# ti-tps61288-junctions-cleaned.net
KiCad netlist of a schematic drawn in Altium Designer
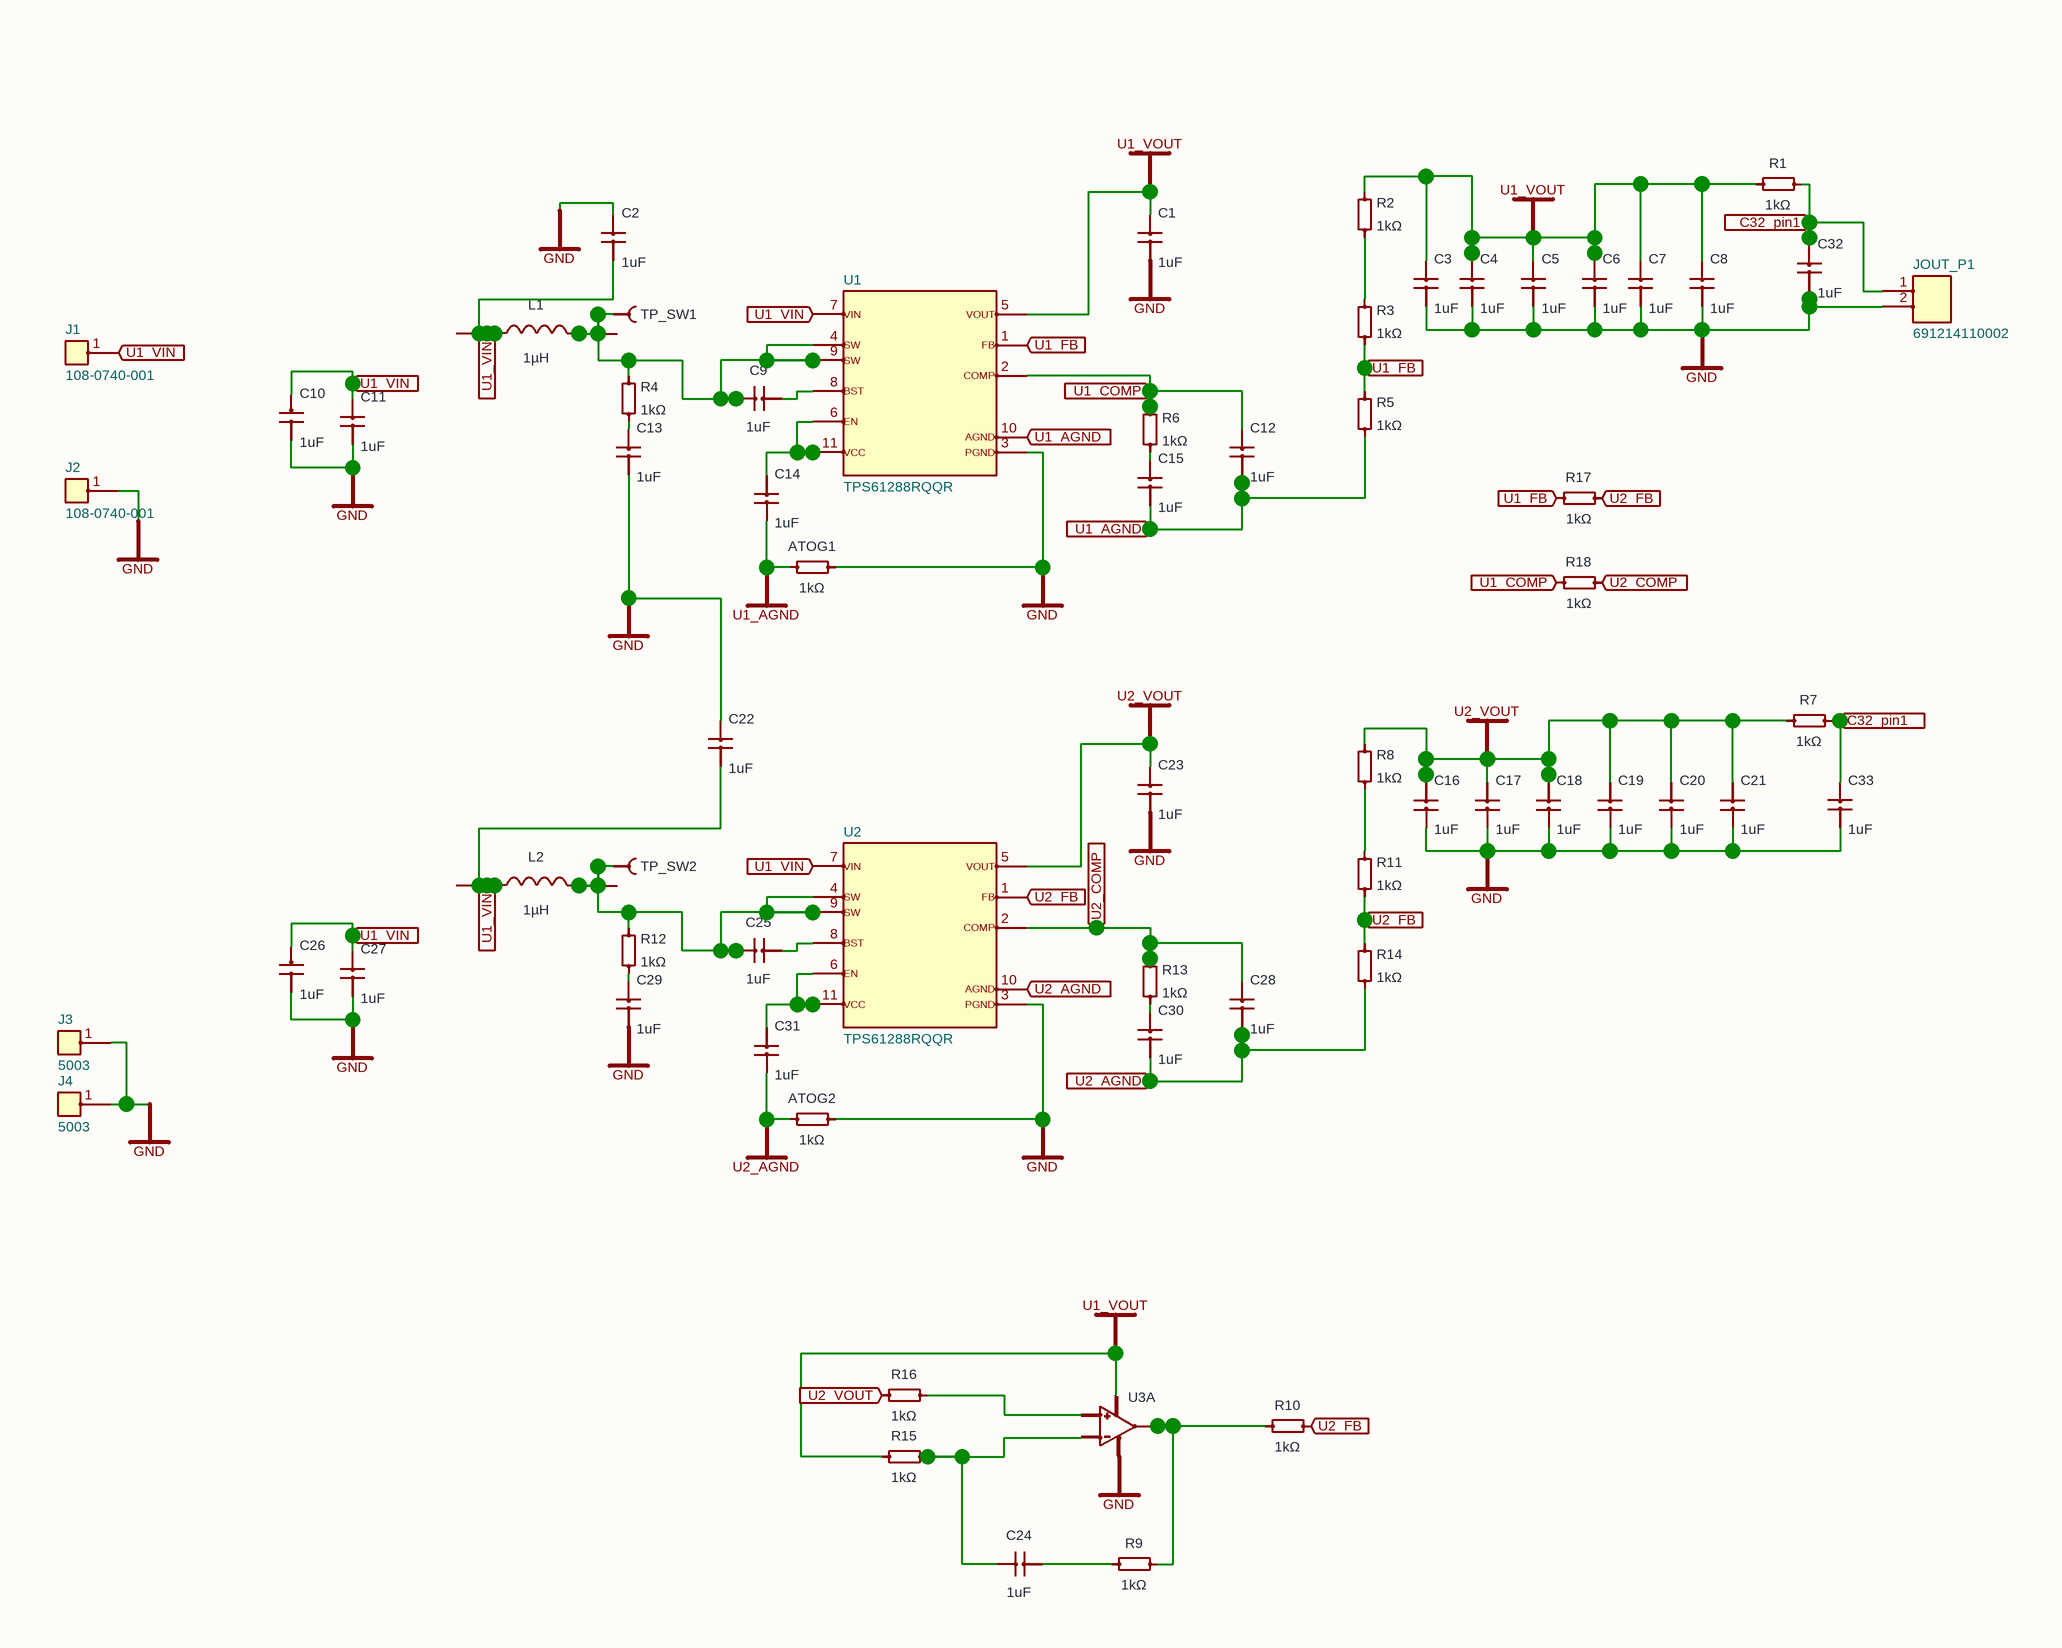
[diagram p0: ti-tps61288-junctions-cleaned.SchDoc]

(export (version "E")
  (design (tool "Eeschema 10.0.6"))
  (components
    (comp (ref "ATOG1") (value "1kΩ") (libsource (lib "altium-import") (part "root_0_boxresistor_left_")))
    (comp (ref "ATOG2") (value "1kΩ") (libsource (lib "altium-import") (part "root_0_boxresistor_left_")))
    (comp (ref "C1") (value "1uF") (libsource (lib "altium-import") (part "root_0_capacitor_down_")))
    (comp (ref "C2") (value "1uF") (libsource (lib "altium-import") (part "root_0_capacitor_down_")))
    (comp (ref "C3") (value "1uF") (libsource (lib "altium-import") (part "root_0_capacitor_down_")))
    (comp (ref "C4") (value "1uF") (libsource (lib "altium-import") (part "root_0_capacitor_down_")))
    (comp (ref "C5") (value "1uF") (libsource (lib "altium-import") (part "root_0_capacitor_down_")))
    (comp (ref "C6") (value "1uF") (libsource (lib "altium-import") (part "root_0_capacitor_down_")))
    (comp (ref "C7") (value "1uF") (libsource (lib "altium-import") (part "root_0_capacitor_down_")))
    (comp (ref "C8") (value "1uF") (libsource (lib "altium-import") (part "root_0_capacitor_down_")))
    (comp (ref "C9") (value "1uF") (libsource (lib "altium-import") (part "root_0_capacitor_right_")))
    (comp (ref "C10") (value "1uF") (libsource (lib "") (part "root_0_capacitor_down__1")))
    (comp (ref "C11") (value "1uF") (libsource (lib "altium-import") (part "root_0_capacitor_down_")))
    (comp (ref "C12") (value "1uF") (libsource (lib "altium-import") (part "root_0_capacitor_down_")))
    (comp (ref "C13") (value "1uF") (libsource (lib "altium-import") (part "root_0_capacitor_down_")))
    (comp (ref "C14") (value "1uF") (libsource (lib "altium-import") (part "root_0_capacitor_up_")))
    (comp (ref "C15") (value "1uF") (libsource (lib "altium-import") (part "root_0_capacitor_down_")))
    (comp (ref "C16") (value "1uF") (libsource (lib "altium-import") (part "root_0_capacitor_up_")))
    (comp (ref "C17") (value "1uF") (libsource (lib "altium-import") (part "root_0_capacitor_up_")))
    (comp (ref "C18") (value "1uF") (libsource (lib "altium-import") (part "root_0_capacitor_up_")))
    (comp (ref "C19") (value "1uF") (libsource (lib "altium-import") (part "root_0_capacitor_up_")))
    (comp (ref "C20") (value "1uF") (libsource (lib "altium-import") (part "root_0_capacitor_up_")))
    (comp (ref "C21") (value "1uF") (libsource (lib "altium-import") (part "root_0_capacitor_up_")))
    (comp (ref "C22") (value "1uF") (libsource (lib "altium-import") (part "root_0_capacitor_down_")))
    (comp (ref "C23") (value "1uF") (libsource (lib "altium-import") (part "root_0_capacitor_down_")))
    (comp (ref "C24") (value "1uF") (libsource (lib "altium-import") (part "root_0_capacitor_left_")))
    (comp (ref "C25") (value "1uF") (libsource (lib "altium-import") (part "root_0_capacitor_right_")))
    (comp (ref "C26") (value "1uF") (libsource (lib "") (part "root_0_capacitor_down__1")))
    (comp (ref "C27") (value "1uF") (libsource (lib "altium-import") (part "root_0_capacitor_down_")))
    (comp (ref "C28") (value "1uF") (libsource (lib "altium-import") (part "root_0_capacitor_down_")))
    (comp (ref "C29") (value "1uF") (libsource (lib "altium-import") (part "root_0_capacitor_down_")))
    (comp (ref "C30") (value "1uF") (libsource (lib "altium-import") (part "root_0_capacitor_down_")))
    (comp (ref "C31") (value "1uF") (libsource (lib "altium-import") (part "root_0_capacitor_up_")))
    (comp (ref "C32") (value "1uF") (libsource (lib "altium-import") (part "root_0_capacitor_down_")))
    (comp (ref "C33") (value "1uF") (libsource (lib "altium-import") (part "root_0_capacitor_down_")))
    (comp (ref "J1") (value "~") (libsource (lib "altium-import") (part "root_0_J1_")))
    (comp (ref "J2") (value "~") (libsource (lib "altium-import") (part "root_0_J2_")))
    (comp (ref "J3") (value "~") (libsource (lib "altium-import") (part "root_0_J3_")))
    (comp (ref "J4") (value "~") (libsource (lib "altium-import") (part "root_0_J4_")))
    (comp (ref "JOUT_P1") (value "~") (libsource (lib "altium-import") (part "root_0_JOUT_P1_")))
    (comp (ref "L1") (value "1µH") (libsource (lib "altium-import") (part "root_0_inductor_right_")))
    (comp (ref "L2") (value "1µH") (libsource (lib "altium-import") (part "root_0_inductor_right_")))
    (comp (ref "R1") (value "1kΩ") (libsource (lib "altium-import") (part "root_0_boxresistor_right_")))
    (comp (ref "R2") (value "1kΩ") (libsource (lib "altium-import") (part "root_0_boxresistor_up_")))
    (comp (ref "R3") (value "1kΩ") (libsource (lib "altium-import") (part "root_0_boxresistor_up_")))
    (comp (ref "R4") (value "1kΩ") (libsource (lib "altium-import") (part "root_0_boxresistor_down_")))
    (comp (ref "R5") (value "1kΩ") (libsource (lib "altium-import") (part "root_0_boxresistor_down_")))
    (comp (ref "R6") (value "1kΩ") (libsource (lib "altium-import") (part "root_0_boxresistor_up_")))
    (comp (ref "R7") (value "1kΩ") (libsource (lib "altium-import") (part "root_0_boxresistor_right_")))
    (comp (ref "R8") (value "1kΩ") (libsource (lib "altium-import") (part "root_0_boxresistor_down_")))
    (comp (ref "R9") (value "1kΩ") (libsource (lib "altium-import") (part "root_0_boxresistor_right_")))
    (comp (ref "R10") (value "1kΩ") (libsource (lib "altium-import") (part "root_0_boxresistor_right_")))
    (comp (ref "R11") (value "1kΩ") (libsource (lib "altium-import") (part "root_0_boxresistor_up_")))
    (comp (ref "R12") (value "1kΩ") (libsource (lib "altium-import") (part "root_0_boxresistor_down_")))
    (comp (ref "R13") (value "1kΩ") (libsource (lib "altium-import") (part "root_0_boxresistor_up_")))
    (comp (ref "R14") (value "1kΩ") (libsource (lib "altium-import") (part "root_0_boxresistor_down_")))
    (comp (ref "R15") (value "1kΩ") (libsource (lib "altium-import") (part "root_0_boxresistor_right_")))
    (comp (ref "R16") (value "1kΩ") (libsource (lib "altium-import") (part "root_0_boxresistor_right_")))
    (comp (ref "R17") (value "1kΩ") (libsource (lib "altium-import") (part "root_0_boxresistor_left_")))
    (comp (ref "R18") (value "1kΩ") (libsource (lib "altium-import") (part "root_0_boxresistor_left_")))
    (comp (ref "TP_SW1") (value "~") (libsource (lib "altium-import") (part "root_0_testpoint_right_")))
    (comp (ref "TP_SW2") (value "~") (libsource (lib "altium-import") (part "root_0_testpoint_right_")))
    (comp (ref "U1") (value "~") (libsource (lib "altium-import") (part "root_0_U1_")))
    (comp (ref "U2") (value "~") (libsource (lib "altium-import") (part "root_0_U2_")))
    (comp (ref "U3A") (value "~") (libsource (lib "altium-import") (part "root_0_opamp_with_power_right_")))
  )
  (nets
    (net (code "1") (name "/C32_pin1") (class "Default")
      (node (ref "C32") (pin "1") (pinfunction "anode_1") (pintype "passive"))
      (node (ref "C33") (pin "1") (pinfunction "anode_1") (pintype "passive"))
      (node (ref "JOUT_P1") (pin "1") (pinfunction "1_1") (pintype "passive"))
      (node (ref "R1") (pin "2") (pinfunction "cathode_2") (pintype "passive"))
      (node (ref "R7") (pin "2") (pinfunction "cathode_2") (pintype "passive"))
    )
    (net (code "2") (name "/U1_COMP") (class "Default")
      (node (ref "C12") (pin "1") (pinfunction "anode_1") (pintype "passive"))
      (node (ref "R18") (pin "2") (pinfunction "cathode_2") (pintype "passive"))
      (node (ref "R6") (pin "2") (pinfunction "cathode_2") (pintype "passive"))
      (node (ref "U1") (pin "2") (pinfunction "COMP_2") (pintype "passive"))
    )
    (net (code "3") (name "/U1_FB") (class "Default")
      (node (ref "R17") (pin "2") (pinfunction "cathode_2") (pintype "passive"))
      (node (ref "R3") (pin "1") (pinfunction "anode_1") (pintype "passive"))
      (node (ref "R5") (pin "1") (pinfunction "anode_1") (pintype "passive"))
      (node (ref "U1") (pin "1") (pinfunction "FB_1") (pintype "passive"))
    )
    (net (code "4") (name "/U1_VIN") (class "Default")
      (node (ref "C10") (pin "1") (pinfunction "anode_1") (pintype "passive"))
      (node (ref "C11") (pin "1") (pinfunction "anode_1") (pintype "passive"))
      (node (ref "C2") (pin "2") (pinfunction "cathode_2") (pintype "passive"))
      (node (ref "C22") (pin "2") (pinfunction "cathode_2") (pintype "passive"))
      (node (ref "C26") (pin "1") (pinfunction "anode_1") (pintype "passive"))
      (node (ref "C27") (pin "1") (pinfunction "anode_1") (pintype "passive"))
      (node (ref "J1") (pin "1") (pinfunction "1_1") (pintype "passive"))
      (node (ref "L1") (pin "1") (pinfunction "anode_1") (pintype "passive"))
      (node (ref "L2") (pin "1") (pinfunction "anode_1") (pintype "passive"))
      (node (ref "U1") (pin "7") (pinfunction "VIN_7") (pintype "passive"))
      (node (ref "U2") (pin "7") (pinfunction "VIN_7") (pintype "passive"))
    )
    (net (code "5") (name "/U2_COMP") (class "Default")
      (node (ref "C28") (pin "1") (pinfunction "anode_1") (pintype "passive"))
      (node (ref "R13") (pin "2") (pinfunction "cathode_2") (pintype "passive"))
      (node (ref "R18") (pin "1") (pinfunction "anode_1") (pintype "passive"))
      (node (ref "U2") (pin "2") (pinfunction "COMP_2") (pintype "passive"))
    )
    (net (code "6") (name "/U2_FB") (class "Default")
      (node (ref "R10") (pin "2") (pinfunction "cathode_2") (pintype "passive"))
      (node (ref "R11") (pin "1") (pinfunction "anode_1") (pintype "passive"))
      (node (ref "R14") (pin "1") (pinfunction "anode_1") (pintype "passive"))
      (node (ref "R17") (pin "1") (pinfunction "anode_1") (pintype "passive"))
      (node (ref "U2") (pin "1") (pinfunction "FB_1") (pintype "passive"))
    )
    (net (code "7") (name "GND") (class "Default")
      (node (ref "ATOG1") (pin "1") (pinfunction "anode_1") (pintype "passive"))
      (node (ref "ATOG2") (pin "1") (pinfunction "anode_1") (pintype "passive"))
      (node (ref "C1") (pin "2") (pinfunction "cathode_2") (pintype "passive"))
      (node (ref "C10") (pin "2") (pinfunction "cathode_2") (pintype "passive"))
      (node (ref "C11") (pin "2") (pinfunction "cathode_2") (pintype "passive"))
      (node (ref "C13") (pin "2") (pinfunction "cathode_2") (pintype "passive"))
      (node (ref "C16") (pin "1") (pinfunction "anode_1") (pintype "passive"))
      (node (ref "C17") (pin "1") (pinfunction "anode_1") (pintype "passive"))
      (node (ref "C18") (pin "1") (pinfunction "anode_1") (pintype "passive"))
      (node (ref "C19") (pin "1") (pinfunction "anode_1") (pintype "passive"))
      (node (ref "C2") (pin "1") (pinfunction "anode_1") (pintype "passive"))
      (node (ref "C20") (pin "1") (pinfunction "anode_1") (pintype "passive"))
      (node (ref "C21") (pin "1") (pinfunction "anode_1") (pintype "passive"))
      (node (ref "C22") (pin "1") (pinfunction "anode_1") (pintype "passive"))
      (node (ref "C23") (pin "2") (pinfunction "cathode_2") (pintype "passive"))
      (node (ref "C26") (pin "2") (pinfunction "cathode_2") (pintype "passive"))
      (node (ref "C27") (pin "2") (pinfunction "cathode_2") (pintype "passive"))
      (node (ref "C29") (pin "2") (pinfunction "cathode_2") (pintype "passive"))
      (node (ref "C3") (pin "2") (pinfunction "cathode_2") (pintype "passive"))
      (node (ref "C32") (pin "2") (pinfunction "cathode_2") (pintype "passive"))
      (node (ref "C33") (pin "2") (pinfunction "cathode_2") (pintype "passive"))
      (node (ref "C4") (pin "2") (pinfunction "cathode_2") (pintype "passive"))
      (node (ref "C5") (pin "2") (pinfunction "cathode_2") (pintype "passive"))
      (node (ref "C6") (pin "2") (pinfunction "cathode_2") (pintype "passive"))
      (node (ref "C7") (pin "2") (pinfunction "cathode_2") (pintype "passive"))
      (node (ref "C8") (pin "2") (pinfunction "cathode_2") (pintype "passive"))
      (node (ref "J2") (pin "1") (pinfunction "1_1") (pintype "passive"))
      (node (ref "J3") (pin "1") (pinfunction "1_1") (pintype "passive"))
      (node (ref "J4") (pin "1") (pinfunction "1_1") (pintype "passive"))
      (node (ref "JOUT_P1") (pin "2") (pinfunction "2_2") (pintype "passive"))
      (node (ref "U1") (pin "3") (pinfunction "PGND_3") (pintype "passive"))
      (node (ref "U2") (pin "3") (pinfunction "PGND_3") (pintype "passive"))
      (node (ref "U3A") (pin "3") (pinfunction "V-_3") (pintype "passive"))
    )
    (net (code "8") (name "Net-(C9-neg)") (class "Default")
      (node (ref "C9") (pin "2") (pinfunction "neg_2") (pintype "passive"))
      (node (ref "U1") (pin "8") (pinfunction "BST_8") (pintype "passive"))
    )
    (net (code "9") (name "Net-(C9-pos)") (class "Default")
      (node (ref "C9") (pin "1") (pinfunction "pos_1") (pintype "passive"))
      (node (ref "L1") (pin "2") (pinfunction "cathode_2") (pintype "passive"))
      (node (ref "R4") (pin "1") (pinfunction "anode_1") (pintype "passive"))
      (node (ref "TP_SW1") (pin "1") (pinfunction "pin1_1") (pintype "passive"))
      (node (ref "U1") (pin "4") (pinfunction "SW_4") (pintype "passive"))
      (node (ref "U1") (pin "9") (pinfunction "SW_9") (pintype "passive"))
    )
    (net (code "10") (name "Net-(C13-anode)") (class "Default")
      (node (ref "C13") (pin "1") (pinfunction "anode_1") (pintype "passive"))
      (node (ref "R4") (pin "2") (pinfunction "cathode_2") (pintype "passive"))
    )
    (net (code "11") (name "Net-(C14-cathode)") (class "Default")
      (node (ref "C14") (pin "2") (pinfunction "cathode_2") (pintype "passive"))
      (node (ref "U1") (pin "11") (pinfunction "VCC_11") (pintype "passive"))
      (node (ref "U1") (pin "6") (pinfunction "EN_6") (pintype "passive"))
    )
    (net (code "12") (name "Net-(C15-anode)") (class "Default")
      (node (ref "C15") (pin "1") (pinfunction "anode_1") (pintype "passive"))
      (node (ref "R6") (pin "1") (pinfunction "anode_1") (pintype "passive"))
    )
    (net (code "13") (name "Net-(C24-neg)") (class "Default")
      (node (ref "C24") (pin "2") (pinfunction "neg_2") (pintype "passive"))
      (node (ref "R15") (pin "2") (pinfunction "cathode_2") (pintype "passive"))
      (node (ref "U3A") (pin "2") (pinfunction "inp2_2") (pintype "passive"))
    )
    (net (code "14") (name "Net-(C24-pos)") (class "Default")
      (node (ref "C24") (pin "1") (pinfunction "pos_1") (pintype "passive"))
      (node (ref "R9") (pin "1") (pinfunction "anode_1") (pintype "passive"))
    )
    (net (code "15") (name "Net-(C25-neg)") (class "Default")
      (node (ref "C25") (pin "2") (pinfunction "neg_2") (pintype "passive"))
      (node (ref "U2") (pin "8") (pinfunction "BST_8") (pintype "passive"))
    )
    (net (code "16") (name "Net-(C25-pos)") (class "Default")
      (node (ref "C25") (pin "1") (pinfunction "pos_1") (pintype "passive"))
      (node (ref "L2") (pin "2") (pinfunction "cathode_2") (pintype "passive"))
      (node (ref "R12") (pin "1") (pinfunction "anode_1") (pintype "passive"))
      (node (ref "TP_SW2") (pin "1") (pinfunction "pin1_1") (pintype "passive"))
      (node (ref "U2") (pin "4") (pinfunction "SW_4") (pintype "passive"))
      (node (ref "U2") (pin "9") (pinfunction "SW_9") (pintype "passive"))
    )
    (net (code "17") (name "Net-(C29-anode)") (class "Default")
      (node (ref "C29") (pin "1") (pinfunction "anode_1") (pintype "passive"))
      (node (ref "R12") (pin "2") (pinfunction "cathode_2") (pintype "passive"))
    )
    (net (code "18") (name "Net-(C30-anode)") (class "Default")
      (node (ref "C30") (pin "1") (pinfunction "anode_1") (pintype "passive"))
      (node (ref "R13") (pin "1") (pinfunction "anode_1") (pintype "passive"))
    )
    (net (code "19") (name "Net-(C31-cathode)") (class "Default")
      (node (ref "C31") (pin "2") (pinfunction "cathode_2") (pintype "passive"))
      (node (ref "U2") (pin "11") (pinfunction "VCC_11") (pintype "passive"))
      (node (ref "U2") (pin "6") (pinfunction "EN_6") (pintype "passive"))
    )
    (net (code "20") (name "Net-(R2-anode)") (class "Default")
      (node (ref "R2") (pin "1") (pinfunction "anode_1") (pintype "passive"))
      (node (ref "R3") (pin "2") (pinfunction "cathode_2") (pintype "passive"))
    )
    (net (code "21") (name "Net-(R10-anode)") (class "Default")
      (node (ref "R10") (pin "1") (pinfunction "anode_1") (pintype "passive"))
      (node (ref "R9") (pin "2") (pinfunction "cathode_2") (pintype "passive"))
      (node (ref "U3A") (pin "4") (pinfunction "out_4") (pintype "passive"))
    )
    (net (code "22") (name "Net-(R11-cathode)") (class "Default")
      (node (ref "R11") (pin "2") (pinfunction "cathode_2") (pintype "passive"))
      (node (ref "R8") (pin "2") (pinfunction "cathode_2") (pintype "passive"))
    )
    (net (code "23") (name "Net-(R16-cathode)") (class "Default")
      (node (ref "R16") (pin "2") (pinfunction "cathode_2") (pintype "passive"))
      (node (ref "U3A") (pin "1") (pinfunction "inp1_1") (pintype "passive"))
    )
    (net (code "24") (name "U1_AGND") (class "Default")
      (node (ref "ATOG1") (pin "2") (pinfunction "cathode_2") (pintype "passive"))
      (node (ref "C12") (pin "2") (pinfunction "cathode_2") (pintype "passive"))
      (node (ref "C14") (pin "1") (pinfunction "anode_1") (pintype "passive"))
      (node (ref "C15") (pin "2") (pinfunction "cathode_2") (pintype "passive"))
      (node (ref "R5") (pin "2") (pinfunction "cathode_2") (pintype "passive"))
      (node (ref "U1") (pin "10") (pinfunction "AGND_10") (pintype "passive"))
    )
    (net (code "25") (name "U1_VOUT") (class "Default")
      (node (ref "C1") (pin "1") (pinfunction "anode_1") (pintype "passive"))
      (node (ref "C3") (pin "1") (pinfunction "anode_1") (pintype "passive"))
      (node (ref "C4") (pin "1") (pinfunction "anode_1") (pintype "passive"))
      (node (ref "C5") (pin "1") (pinfunction "anode_1") (pintype "passive"))
      (node (ref "C6") (pin "1") (pinfunction "anode_1") (pintype "passive"))
      (node (ref "C7") (pin "1") (pinfunction "anode_1") (pintype "passive"))
      (node (ref "C8") (pin "1") (pinfunction "anode_1") (pintype "passive"))
      (node (ref "R1") (pin "1") (pinfunction "anode_1") (pintype "passive"))
      (node (ref "R15") (pin "1") (pinfunction "anode_1") (pintype "passive"))
      (node (ref "R2") (pin "2") (pinfunction "cathode_2") (pintype "passive"))
      (node (ref "U1") (pin "5") (pinfunction "VOUT_5") (pintype "passive"))
      (node (ref "U3A") (pin "5") (pinfunction "V+_5") (pintype "passive"))
    )
    (net (code "26") (name "U2_AGND") (class "Default")
      (node (ref "ATOG2") (pin "2") (pinfunction "cathode_2") (pintype "passive"))
      (node (ref "C28") (pin "2") (pinfunction "cathode_2") (pintype "passive"))
      (node (ref "C30") (pin "2") (pinfunction "cathode_2") (pintype "passive"))
      (node (ref "C31") (pin "1") (pinfunction "anode_1") (pintype "passive"))
      (node (ref "R14") (pin "2") (pinfunction "cathode_2") (pintype "passive"))
      (node (ref "U2") (pin "10") (pinfunction "AGND_10") (pintype "passive"))
    )
    (net (code "27") (name "U2_VOUT") (class "Default")
      (node (ref "C16") (pin "2") (pinfunction "cathode_2") (pintype "passive"))
      (node (ref "C17") (pin "2") (pinfunction "cathode_2") (pintype "passive"))
      (node (ref "C18") (pin "2") (pinfunction "cathode_2") (pintype "passive"))
      (node (ref "C19") (pin "2") (pinfunction "cathode_2") (pintype "passive"))
      (node (ref "C20") (pin "2") (pinfunction "cathode_2") (pintype "passive"))
      (node (ref "C21") (pin "2") (pinfunction "cathode_2") (pintype "passive"))
      (node (ref "C23") (pin "1") (pinfunction "anode_1") (pintype "passive"))
      (node (ref "R16") (pin "1") (pinfunction "anode_1") (pintype "passive"))
      (node (ref "R7") (pin "1") (pinfunction "anode_1") (pintype "passive"))
      (node (ref "R8") (pin "1") (pinfunction "anode_1") (pintype "passive"))
      (node (ref "U2") (pin "5") (pinfunction "VOUT_5") (pintype "passive"))
    )
  )
)
